# Control_Unit_and_Power.net
KiCad netlist of a schematic drawn in Altium Designer
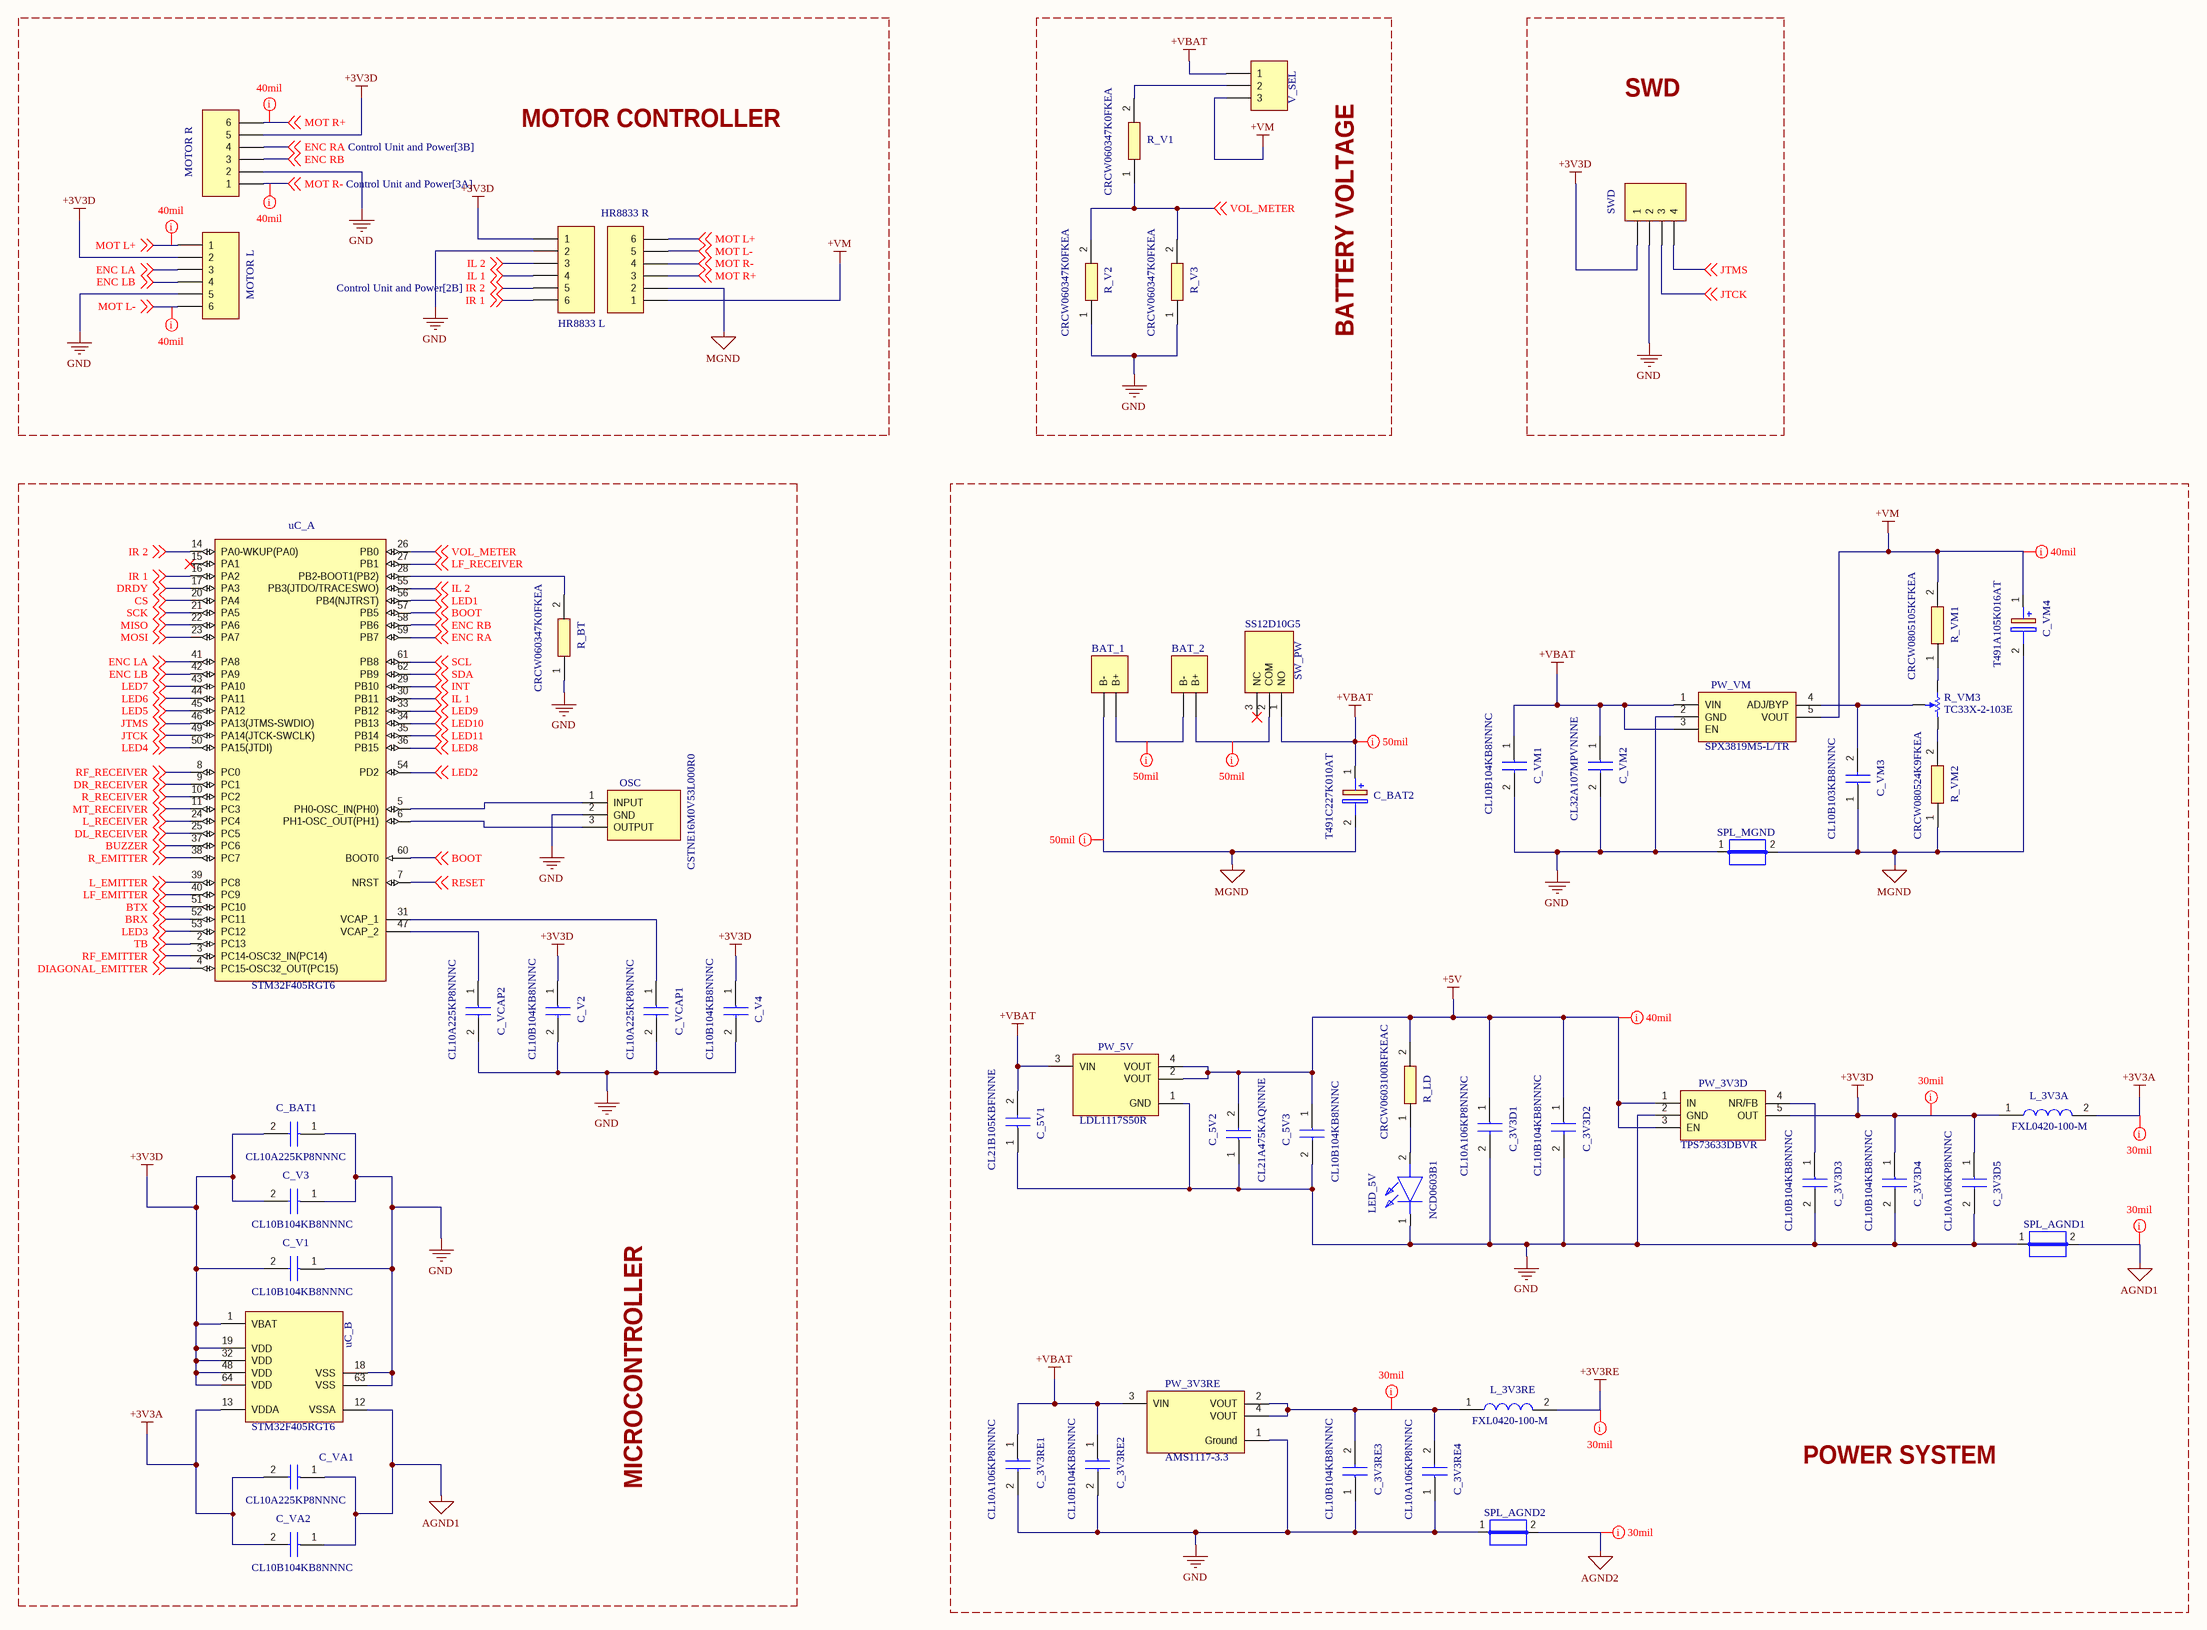
[diagram p0: Control Unit and Power.SchDoc]

(export (version "E")
  (design (tool "Eeschema 10.0.6"))
  (components
    (comp (ref "BAT_1")
      (value "Header 2")
      (footprint "MY_6410-02")
      (description "Header, 2-Pin")
      (fields (field (name "ASID PART NUMBER") "Header 2-AS"))
      (libsource (lib "Mylib+Rev+4") (part "Header 2"))
    )
    (comp (ref "BAT_2")
      (value "Header 2")
      (footprint "MY_6410-02")
      (description "Header, 2-Pin")
      (fields (field (name "ASID PART NUMBER") "Header 2-AS"))
      (libsource (lib "Mylib+Rev+4") (part "Header 2"))
    )
    (comp (ref "C_3V3D1")
      (value "CL10A106KP8NNNC")
      (footprint "SamacSys:CAPC1608X90N")
      (description "Capacitor")
      (fields (field (name "MOUSER PART NUMBER") "187-CL10A106KP8NNNC"))
      (libsource (lib "*") (part "CL10A106KP8NNNC"))
    )
    (comp (ref "C_3V3D2")
      (value "CL10B104KB8NNNC")
      (footprint "SamacSys:CAPC1608X90N")
      (description "Capacitor")
      (fields (field (name "MOUSER PART NUMBER") "187-CL10B104KB8NNNC"))
      (libsource (lib "*") (part "CL10B104KB8NNNC"))
    )
    (comp (ref "C_3V3D3")
      (value "CL10B104KB8NNNC")
      (footprint "SamacSys:CAPC1608X90N")
      (description "Capacitor")
      (fields (field (name "MOUSER PART NUMBER") "187-CL10B104KB8NNNC"))
      (libsource (lib "*") (part "CL10B104KB8NNNC"))
    )
    (comp (ref "C_3V3D4")
      (value "CL10B104KB8NNNC")
      (footprint "SamacSys:CAPC1608X90N")
      (description "Capacitor")
      (fields (field (name "MOUSER PART NUMBER") "187-CL10B104KB8NNNC"))
      (libsource (lib "*") (part "CL10B104KB8NNNC"))
    )
    (comp (ref "C_3V3D5")
      (value "CL10A106KP8NNNC")
      (footprint "SamacSys:CAPC1608X90N")
      (description "Capacitor")
      (fields (field (name "MOUSER PART NUMBER") "187-CL10A106KP8NNNC"))
      (libsource (lib "*") (part "CL10A106KP8NNNC"))
    )
    (comp (ref "C_3V3RE1")
      (value "CL10A106KP8NNNC")
      (footprint "SamacSys:CAPC1608X90N")
      (description "Capacitor")
      (fields (field (name "MOUSER PART NUMBER") "187-CL10A106KP8NNNC"))
      (libsource (lib "*") (part "CL10A106KP8NNNC"))
    )
    (comp (ref "C_3V3RE2")
      (value "CL10B104KB8NNNC")
      (footprint "SamacSys:CAPC1608X90N")
      (description "Capacitor")
      (fields (field (name "MOUSER PART NUMBER") "187-CL10B104KB8NNNC"))
      (libsource (lib "*") (part "CL10B104KB8NNNC"))
    )
    (comp (ref "C_3V3RE3")
      (value "CL10B104KB8NNNC")
      (footprint "SamacSys:CAPC1608X90N")
      (description "Capacitor")
      (fields (field (name "MOUSER PART NUMBER") "187-CL10B104KB8NNNC"))
      (libsource (lib "*") (part "CL10B104KB8NNNC"))
    )
    (comp (ref "C_3V3RE4")
      (value "CL10A106KP8NNNC")
      (footprint "SamacSys:CAPC1608X90N")
      (description "Capacitor")
      (fields (field (name "MOUSER PART NUMBER") "187-CL10A106KP8NNNC"))
      (libsource (lib "*") (part "CL10A106KP8NNNC"))
    )
    (comp (ref "C_5V1")
      (value "CL21B105KBFNNNE")
      (footprint "SamacSys:CAPC2012X135N")
      (description "Capacitor")
      (fields (field (name "MOUSER PART NUMBER") "187-CL21B105KBFNNNE"))
      (libsource (lib "*") (part "CL21B105KBFNNNE"))
    )
    (comp (ref "C_5V2")
      (value "CL21A475KAQNNNE")
      (footprint "SamacSys:CAPC2012X140N")
      (description "Capacitor")
      (fields (field (name "MOUSER PART NUMBER") "187-CL21A475KAQNNNE"))
      (libsource (lib "*") (part "CL21A475KAQNNNE"))
    )
    (comp (ref "C_5V3")
      (value "CL10B104KB8NNNC")
      (footprint "SamacSys:CAPC1608X90N")
      (description "Capacitor")
      (fields (field (name "MOUSER PART NUMBER") "187-CL10B104KB8NNNC"))
      (libsource (lib "*") (part "CL10B104KB8NNNC"))
    )
    (comp (ref "C_BAT1")
      (value "CL10A225KP8NNNC")
      (footprint "SamacSys:CAPC1608X90N")
      (description "Capacitor")
      (fields (field (name "MOUSER PART NUMBER") "187-CL10A225KP8NNNC"))
      (libsource (lib "*") (part "CL10A225KP8NNNC"))
    )
    (comp (ref "C_BAT2")
      (value "T491C227K010AT")
      (footprint "SamacSys:T491C")
      (description "Capacitor Polarised")
      (fields (field (name "MOUSER PART NUMBER") "80-T491C227K010AT"))
      (libsource (lib "*") (part "T491C227K010AT"))
    )
    (comp (ref "C_V1")
      (value "CL10B104KB8NNNC")
      (footprint "SamacSys:CAPC1608X90N")
      (description "Capacitor")
      (fields (field (name "MOUSER PART NUMBER") "187-CL10B104KB8NNNC"))
      (libsource (lib "*") (part "CL10B104KB8NNNC"))
    )
    (comp (ref "C_V2")
      (value "CL10B104KB8NNNC")
      (footprint "SamacSys:CAPC1608X90N")
      (description "Capacitor")
      (fields (field (name "MOUSER PART NUMBER") "187-CL10B104KB8NNNC"))
      (libsource (lib "*") (part "CL10B104KB8NNNC"))
    )
    (comp (ref "C_V3")
      (value "CL10B104KB8NNNC")
      (footprint "SamacSys:CAPC1608X90N")
      (description "Capacitor")
      (fields (field (name "MOUSER PART NUMBER") "187-CL10B104KB8NNNC"))
      (libsource (lib "*") (part "CL10B104KB8NNNC"))
    )
    (comp (ref "C_V4")
      (value "CL10B104KB8NNNC")
      (footprint "SamacSys:CAPC1608X90N")
      (description "Capacitor")
      (fields (field (name "MOUSER PART NUMBER") "187-CL10B104KB8NNNC"))
      (libsource (lib "*") (part "CL10B104KB8NNNC"))
    )
    (comp (ref "C_VA1")
      (value "CL10A225KP8NNNC")
      (footprint "SamacSys:CAPC1608X90N")
      (description "Capacitor")
      (fields (field (name "MOUSER PART NUMBER") "187-CL10A225KP8NNNC"))
      (libsource (lib "*") (part "CL10A225KP8NNNC"))
    )
    (comp (ref "C_VA2")
      (value "CL10B104KB8NNNC")
      (footprint "SamacSys:CAPC1608X90N")
      (description "Capacitor")
      (fields (field (name "MOUSER PART NUMBER") "187-CL10B104KB8NNNC"))
      (libsource (lib "*") (part "CL10B104KB8NNNC"))
    )
    (comp (ref "C_VCAP1")
      (value "CL10A225KP8NNNC")
      (footprint "SamacSys:CAPC1608X90N")
      (description "Capacitor")
      (fields (field (name "MOUSER PART NUMBER") "187-CL10A225KP8NNNC"))
      (libsource (lib "*") (part "CL10A225KP8NNNC"))
    )
    (comp (ref "C_VCAP2")
      (value "CL10A225KP8NNNC")
      (footprint "SamacSys:CAPC1608X90N")
      (description "Capacitor")
      (fields (field (name "MOUSER PART NUMBER") "187-CL10A225KP8NNNC"))
      (libsource (lib "*") (part "CL10A225KP8NNNC"))
    )
    (comp (ref "C_VM1")
      (value "CL10B104KB8NNNC")
      (footprint "SamacSys:CAPC1608X90N")
      (description "Capacitor")
      (fields (field (name "MOUSER PART NUMBER") "187-CL10B104KB8NNNC"))
      (libsource (lib "*") (part "CL10B104KB8NNNC"))
    )
    (comp (ref "C_VM2")
      (value "CL32A107MPVNNNE")
      (footprint "SamacSys:CAPC3225X280N")
      (description "Capacitor")
      (fields (field (name "MOUSER PART NUMBER") "187-CL32A107MPVNNNE"))
      (libsource (lib "*") (part "CL32A107MPVNNNE"))
    )
    (comp (ref "C_VM3")
      (value "CL10B103KB8NNNC")
      (footprint "SamacSys:CAPC1608X90N")
      (description "Capacitor")
      (fields (field (name "MOUSER PART NUMBER") "187-CL10B103KB8NNNC"))
      (libsource (lib "*") (part "CL10B103KB8NNNC"))
    )
    (comp (ref "C_VM4")
      (value "T491A105K016AT")
      (footprint "SamacSys:T491A")
      (description "Capacitor Polarised")
      (fields (field (name "MOUSER PART NUMBER") "80-T491A105K016"))
      (libsource (lib "*") (part "T491A105K016AT"))
    )
    (comp (ref "HR8833 L")
      (value "Header 6")
      (footprint "My_1X06")
      (description "Header, 6-Pin")
      (fields (field (name "ASID PART NUMBER") "Header 6-AS"))
      (libsource (lib "Mylib+Rev+4") (part "Header 6"))
    )
    (comp (ref "HR8833 R")
      (value "Header 6")
      (footprint "My_1X06")
      (description "Header, 6-Pin")
      (fields (field (name "ASID PART NUMBER") "Header 6-AS"))
      (libsource (lib "") (part "Header 6_1"))
    )
    (comp (ref "LED_5V")
      (value "NCD0603B1")
      (footprint "SamacSys:LEDC1608X40N")
      (fields
        (field (name "MANUFACTURER_PART_NUMBER") "LB Q39E-L2OO-35-1")
        (field (name "MOUSER PART NUMBER") "720-LBQ39EL2N2351")
      )
      (libsource (lib "*") (part "LB_Q39E-L2OO-35-1"))
    )
    (comp (ref "L_3V3A")
      (value "FXL0420-100-M")
      (footprint "SamacSys:INDPM4441X120N")
      (description "1.6A 10uH Integrated molded inductor ±20% 2.2A SMD,4.2x4.4mm Power Inductors ROHS")
      (fields
        (field (name "MANUFACTURER_PART_NUMBER") "PM4546.331NLT")
        (field (name "MOUSER PART NUMBER") "673-PM4546.331NLT")
      )
      (libsource (lib "*") (part "PM4546.331NLT"))
    )
    (comp (ref "L_3V3RE")
      (value "FXL0420-100-M")
      (footprint "SamacSys:INDPM4441X120N")
      (description "1.6A 10uH Integrated molded inductor ±20% 2.2A SMD,4.2x4.4mm Power Inductors ROHS")
      (fields
        (field (name "MANUFACTURER_PART_NUMBER") "PM4546.331NLT")
        (field (name "MOUSER PART NUMBER") "673-PM4546.331NLT")
      )
      (libsource (lib "*") (part "PM4546.331NLT"))
    )
    (comp (ref "MOTOR L")
      (value "Header 6")
      (footprint "MY_53253-0670")
      (description "Header, 6-Pin")
      (fields (field (name "ASID PART NUMBER") "Header 6-AS"))
      (libsource (lib "Mylib+Rev+4") (part "Header 6"))
    )
    (comp (ref "MOTOR R")
      (value "Header 6")
      (footprint "MY_53253-0670")
      (description "Header, 6-Pin")
      (fields (field (name "ASID PART NUMBER") "Header 6-AS"))
      (libsource (lib "") (part "Header 6_1"))
    )
    (comp (ref "OSC")
      (value "CSTNE16M0V53L000R0")
      (footprint "SamacSys:CSTNE16M0V53L000R0")
      (description "Crystal or Oscillator")
      (fields (field (name "MOUSER PART NUMBER") "81-CSTNE16M0V53L000R"))
      (libsource (lib "*") (part "CSTNE16M0V53L000R0"))
    )
    (comp (ref "PW_3V3D")
      (value "TPS73633DBVR")
      (footprint "SamacSys:SOT95P280X145-5N")
      (description "Integrated Circuit")
      (fields (field (name "MOUSER PART NUMBER") "595-TPS73633DBVR"))
      (libsource (lib "*") (part "TPS73633DBVR"))
    )
    (comp (ref "PW_3V3RE")
      (value "AMS1117-3.3")
      (footprint "FP-AMS1117-IPC_C")
      (description "LDO Voltage Regulators 1A, 3.3V")
      (fields
        (field (name "OCTOPART") "https://octopart.com/ams1117-3.3-advanced+monolithic+systems-25899300")
        (field (name "MANUFACTURER") "Advanced Monolithic Systems")
      )
      (libsource (lib "Altium Content Vault") (part "8bdbb5f8e77002000e30dd2845d0354"))
    )
    (comp (ref "PW_5V")
      (value "LDL1117S50R")
      (footprint "FP-SOT-223-0046067_14-MFG")
      (description "IC REG LINEAR 5V 1.2A SOT223")
      (fields
        (field (name "OCTOPART") "https://octopart.com/ldl1117s50r-stmicroelectronics-81876164")
        (field (name "MANUFACTURER") "STMicroelectronics")
      )
      (libsource (lib "Altium Content Vault") (part "a368f1d72361ca9956852d636243424"))
    )
    (comp (ref "PW_VM")
      (value "SPX3819M5-L/TR")
      (footprint "SamacSys:SOT95P280X145-5N")
      (description "Integrated Circuit")
      (fields (field (name "MOUSER PART NUMBER") "701-SPX3819M5-L/TR"))
      (libsource (lib "*") (part "SPX3819M5-L_TR"))
    )
    (comp (ref "R_BT")
      (value "CRCW060347K0FKEA")
      (footprint "SamacSys:RESC1608X50N")
      (description "Resistor")
      (fields (field (name "MOUSER PART NUMBER") "71-CRCW0603-47K-E3"))
      (libsource (lib "*") (part "CRCW060347K0FKEA"))
    )
    (comp (ref "R_LD")
      (value "CRCW0603100RFKEAC")
      (footprint "SamacSys:RESC1608X55N")
      (description "Resistor")
      (fields (field (name "MOUSER PART NUMBER") "71-CRCW0603100RFKEAC"))
      (libsource (lib "*") (part "CRCW0603100RFKEAC"))
    )
    (comp (ref "R_V1")
      (value "CRCW060347K0FKEA")
      (footprint "SamacSys:RESC1608X50N")
      (description "Resistor")
      (fields (field (name "MOUSER PART NUMBER") "71-CRCW0603-47K-E3"))
      (libsource (lib "*") (part "CRCW060347K0FKEA"))
    )
    (comp (ref "R_V2")
      (value "CRCW060347K0FKEA")
      (footprint "SamacSys:RESC1608X50N")
      (description "Resistor")
      (fields (field (name "MOUSER PART NUMBER") "71-CRCW0603-47K-E3"))
      (libsource (lib "*") (part "CRCW060347K0FKEA"))
    )
    (comp (ref "R_V3")
      (value "CRCW060347K0FKEA")
      (footprint "SamacSys:RESC1608X50N")
      (description "Resistor")
      (fields (field (name "MOUSER PART NUMBER") "71-CRCW0603-47K-E3"))
      (libsource (lib "*") (part "CRCW060347K0FKEA"))
    )
    (comp (ref "R_VM1")
      (value "CRCW0805105KFKEA")
      (footprint "SamacSys:RESC2012X50N")
      (description "Resistor")
      (fields (field (name "MOUSER PART NUMBER") "71-CRCW0805-105K-E3"))
      (libsource (lib "*") (part "CRCW0805105KFKEA"))
    )
    (comp (ref "R_VM2")
      (value "CRCW080524K9FKEA")
      (footprint "SamacSys:RESC2012X50N")
      (description "Resistor")
      (fields (field (name "MOUSER PART NUMBER") "71-CRCW0805-24.9K-E3"))
      (libsource (lib "*") (part "CRCW080524K9FKEA"))
    )
    (comp (ref "R_VM3")
      (value "TC33X-2-103E")
      (footprint "BOUR-TC33X-2_V")
      (description "Trimming Potentiometer, 10000 Ohm, -40 to 100 degC, 3-Pin SMD, RoHS, Tape and Reel")
      (fields (field (name "TOLERANCE") "25%") (field (name "MANUFACTURER") "Bourns"))
      (libsource (lib "Altium Content Vault") (part "RES-ADJ-3_A"))
    )
    (comp (ref "SPL_AGND1")
      (value "JUMPER")
      (footprint "JUMPER")
      (libsource (lib "University of Moratuwa") (part "JUMPER"))
    )
    (comp (ref "SPL_AGND2")
      (value "JUMPER")
      (footprint "JUMPER")
      (libsource (lib "University of Moratuwa") (part "JUMPER"))
    )
    (comp (ref "SPL_MGND")
      (value "JUMPER")
      (footprint "JUMPER")
      (libsource (lib "University of Moratuwa") (part "JUMPER"))
    )
    (comp (ref "SWD")
      (value "Header 4")
      (footprint "MY_FE04")
      (description "Header, 4-Pin")
      (fields (field (name "ASID PART NUMBER") "Header 4-AS"))
      (libsource (lib "Mylib+Rev+4") (part "Header 4"))
    )
    (comp (ref "SW_PW")
      (value "SS12D10G5")
      (footprint "SamacSys:GH36P010001")
      (description "Bend insert 2A Single Pole Double Throw (SPDT) 125V 3000 times Black Plugin Slide Switches ROHS")
      (fields
        (field (name "MANUFACTURER_PART_NUMBER") "GH36P010001")
        (field (name "MOUSER PART NUMBER") "642-GH36P010001")
      )
      (libsource (lib "*") (part "GH36P010001"))
    )
    (comp (ref "uC_")
      (value "STM32F405RGT6")
      (footprint "STM-LQFP64_V")
      (fields (field (name "MANUFACTURER") "STMicroelectronics"))
      (libsource (lib "Altium Content Vault") (part "MC-ARM-STM32F4X5-SQ64"))
    )
    (comp (ref "V_SEL")
      (value "Header 3")
      (footprint "My_1X03")
      (description "Header, 3-Pin")
      (fields (field (name "ASID PART NUMBER") "Header 3-AS"))
      (libsource (lib "Mylib+Rev+4") (part "Header 3"))
    )
  )
  (nets
    (net (code "1") (name "+3V3A") (class "Default")
      (node (ref "C_VA1") (pin "2") (pinfunction "2_2") (pintype "passive"))
      (node (ref "C_VA2") (pin "2") (pinfunction "2_2") (pintype "passive"))
      (node (ref "L_3V3A") (pin "2") (pinfunction "2_2") (pintype "passive"))
      (node (ref "uC_") (pin "13") (pinfunction "VDDA_13") (pintype "power_in"))
    )
    (net (code "2") (name "+3V3D") (class "Default")
      (node (ref "C_3V3D4") (pin "1") (pinfunction "1_1") (pintype "passive"))
      (node (ref "C_3V3D5") (pin "1") (pinfunction "1_1") (pintype "passive"))
      (node (ref "C_BAT1") (pin "2") (pinfunction "2_2") (pintype "passive"))
      (node (ref "C_V1") (pin "2") (pinfunction "2_2") (pintype "passive"))
      (node (ref "C_V2") (pin "1") (pinfunction "1_1") (pintype "passive"))
      (node (ref "C_V3") (pin "2") (pinfunction "2_2") (pintype "passive"))
      (node (ref "C_V4") (pin "1") (pinfunction "1_1") (pintype "passive"))
      (node (ref "HR8833 L") (pin "1") (pinfunction "1_1") (pintype "passive"))
      (node (ref "L_3V3A") (pin "1") (pinfunction "1_1") (pintype "passive"))
      (node (ref "MOTOR L") (pin "2") (pinfunction "2_2") (pintype "passive"))
      (node (ref "MOTOR R") (pin "5") (pinfunction "5_5") (pintype "passive"))
      (node (ref "PW_3V3D") (pin "5") (pinfunction "OUT_5") (pintype "passive"))
      (node (ref "SWD") (pin "1") (pinfunction "1_1") (pintype "passive"))
      (node (ref "uC_") (pin "1") (pinfunction "VBAT_1") (pintype "power_in"))
      (node (ref "uC_") (pin "19") (pinfunction "VDD_19") (pintype "power_in"))
      (node (ref "uC_") (pin "32") (pinfunction "VDD_32") (pintype "power_in"))
      (node (ref "uC_") (pin "48") (pinfunction "VDD_48") (pintype "power_in"))
      (node (ref "uC_") (pin "64") (pinfunction "VDD_64") (pintype "power_in"))
    )
    (net (code "3") (name "+3V3RE") (class "Default")
      (node (ref "L_3V3RE") (pin "2") (pinfunction "2_2") (pintype "passive"))
    )
    (net (code "4") (name "+5V") (class "Default")
      (node (ref "C_3V3D1") (pin "1") (pinfunction "1_1") (pintype "passive"))
      (node (ref "C_3V3D2") (pin "1") (pinfunction "1_1") (pintype "passive"))
      (node (ref "C_5V2") (pin "2") (pinfunction "2_2") (pintype "passive"))
      (node (ref "C_5V3") (pin "1") (pinfunction "1_1") (pintype "passive"))
      (node (ref "PW_3V3D") (pin "1") (pinfunction "IN_1") (pintype "passive"))
      (node (ref "PW_3V3D") (pin "3") (pinfunction "EN_3") (pintype "passive"))
      (node (ref "PW_5V") (pin "2") (pinfunction "VOUT_2") (pintype "power_in"))
      (node (ref "PW_5V") (pin "4") (pinfunction "VOUT_4") (pintype "power_in"))
      (node (ref "R_LD") (pin "2") (pinfunction "2_2") (pintype "passive"))
    )
    (net (code "5") (name "+VBAT") (class "Default")
      (node (ref "C_3V3RE1") (pin "1") (pinfunction "1_1") (pintype "passive"))
      (node (ref "C_3V3RE2") (pin "1") (pinfunction "1_1") (pintype "passive"))
      (node (ref "C_5V1") (pin "2") (pinfunction "2_2") (pintype "passive"))
      (node (ref "C_BAT2") (pin "1") (pinfunction "+_1") (pintype "passive"))
      (node (ref "C_VM1") (pin "1") (pinfunction "1_1") (pintype "passive"))
      (node (ref "C_VM2") (pin "1") (pinfunction "1_1") (pintype "passive"))
      (node (ref "PW_3V3RE") (pin "3") (pinfunction "VIN_3") (pintype "power_in"))
      (node (ref "PW_5V") (pin "3") (pinfunction "VIN_3") (pintype "power_in"))
      (node (ref "PW_VM") (pin "1") (pinfunction "VIN_1") (pintype "passive"))
      (node (ref "PW_VM") (pin "3") (pinfunction "EN_3") (pintype "passive"))
      (node (ref "SW_PW") (pin "1") (pinfunction "NO_1") (pintype "passive"))
      (node (ref "V_SEL") (pin "1") (pinfunction "1_1") (pintype "passive"))
    )
    (net (code "6") (name "+VM") (class "Default")
      (node (ref "C_VM4") (pin "1") (pinfunction "+_1") (pintype "passive"))
      (node (ref "HR8833 R") (pin "1") (pinfunction "1_1") (pintype "passive"))
      (node (ref "PW_VM") (pin "5") (pinfunction "VOUT_5") (pintype "passive"))
      (node (ref "R_VM1") (pin "2") (pinfunction "2_2") (pintype "passive"))
      (node (ref "V_SEL") (pin "3") (pinfunction "3_3") (pintype "passive"))
    )
    (net (code "7") (name "AGND1") (class "Default")
      (node (ref "C_VA1") (pin "1") (pinfunction "1_1") (pintype "passive"))
      (node (ref "C_VA2") (pin "1") (pinfunction "1_1") (pintype "passive"))
      (node (ref "SPL_AGND1") (pin "2") (pinfunction "2_2") (pintype "passive"))
      (node (ref "uC_") (pin "12") (pinfunction "VSSA_12") (pintype "power_in"))
    )
    (net (code "8") (name "AGND2") (class "Default")
      (node (ref "SPL_AGND2") (pin "2") (pinfunction "2_2") (pintype "passive"))
    )
    (net (code "9") (name "BOOT") (class "Default")
      (node (ref "uC_") (pin "57") (pinfunction "PB5_57") (pintype "bidirectional"))
      (node (ref "uC_") (pin "60") (pinfunction "BOOT0_60") (pintype "input"))
    )
    (net (code "10") (name "BRX") (class "Default")
      (node (ref "uC_") (pin "52") (pinfunction "PC11_52") (pintype "bidirectional"))
    )
    (net (code "11") (name "BTX") (class "Default")
      (node (ref "uC_") (pin "51") (pinfunction "PC10_51") (pintype "bidirectional"))
    )
    (net (code "12") (name "BUZZER") (class "Default")
      (node (ref "uC_") (pin "37") (pinfunction "PC6_37") (pintype "bidirectional"))
    )
    (net (code "13") (name "CS") (class "Default")
      (node (ref "uC_") (pin "20") (pinfunction "PA4_20") (pintype "bidirectional"))
    )
    (net (code "14") (name "DIAGONAL_EMITTER") (class "Default")
      (node (ref "uC_") (pin "4") (pinfunction "PC15-OSC32_OUT(PC15)_4") (pintype "bidirectional"))
    )
    (net (code "15") (name "DL_RECEIVER") (class "Default")
      (node (ref "uC_") (pin "25") (pinfunction "PC5_25") (pintype "bidirectional"))
    )
    (net (code "16") (name "DRDY") (class "Default")
      (node (ref "uC_") (pin "17") (pinfunction "PA3_17") (pintype "bidirectional"))
    )
    (net (code "17") (name "DR_RECEIVER") (class "Default")
      (node (ref "uC_") (pin "9") (pinfunction "PC1_9") (pintype "bidirectional"))
    )
    (net (code "18") (name "ENC LA") (class "Default")
      (node (ref "MOTOR L") (pin "3") (pinfunction "3_3") (pintype "passive"))
      (node (ref "uC_") (pin "41") (pinfunction "PA8_41") (pintype "bidirectional"))
    )
    (net (code "19") (name "ENC LB") (class "Default")
      (node (ref "MOTOR L") (pin "4") (pinfunction "4_4") (pintype "passive"))
      (node (ref "uC_") (pin "42") (pinfunction "PA9_42") (pintype "bidirectional"))
    )
    (net (code "20") (name "ENC RA") (class "Default")
      (node (ref "MOTOR R") (pin "4") (pinfunction "4_4") (pintype "passive"))
      (node (ref "uC_") (pin "59") (pinfunction "PB7_59") (pintype "bidirectional"))
    )
    (net (code "21") (name "ENC RB") (class "Default")
      (node (ref "MOTOR R") (pin "3") (pinfunction "3_3") (pintype "passive"))
      (node (ref "uC_") (pin "58") (pinfunction "PB6_58") (pintype "bidirectional"))
    )
    (net (code "22") (name "GND") (class "Default")
      (node (ref "C_3V3D1") (pin "2") (pinfunction "2_2") (pintype "passive"))
      (node (ref "C_3V3D2") (pin "2") (pinfunction "2_2") (pintype "passive"))
      (node (ref "C_3V3D3") (pin "2") (pinfunction "2_2") (pintype "passive"))
      (node (ref "C_3V3D4") (pin "2") (pinfunction "2_2") (pintype "passive"))
      (node (ref "C_3V3D5") (pin "2") (pinfunction "2_2") (pintype "passive"))
      (node (ref "C_3V3RE1") (pin "2") (pinfunction "2_2") (pintype "passive"))
      (node (ref "C_3V3RE2") (pin "2") (pinfunction "2_2") (pintype "passive"))
      (node (ref "C_3V3RE3") (pin "1") (pinfunction "1_1") (pintype "passive"))
      (node (ref "C_3V3RE4") (pin "1") (pinfunction "1_1") (pintype "passive"))
      (node (ref "C_5V1") (pin "1") (pinfunction "1_1") (pintype "passive"))
      (node (ref "C_5V2") (pin "1") (pinfunction "1_1") (pintype "passive"))
      (node (ref "C_5V3") (pin "2") (pinfunction "2_2") (pintype "passive"))
      (node (ref "C_BAT1") (pin "1") (pinfunction "1_1") (pintype "passive"))
      (node (ref "C_V1") (pin "1") (pinfunction "1_1") (pintype "passive"))
      (node (ref "C_V2") (pin "2") (pinfunction "2_2") (pintype "passive"))
      (node (ref "C_V3") (pin "1") (pinfunction "1_1") (pintype "passive"))
      (node (ref "C_V4") (pin "2") (pinfunction "2_2") (pintype "passive"))
      (node (ref "C_VCAP1") (pin "2") (pinfunction "2_2") (pintype "passive"))
      (node (ref "C_VCAP2") (pin "2") (pinfunction "2_2") (pintype "passive"))
      (node (ref "C_VM1") (pin "2") (pinfunction "2_2") (pintype "passive"))
      (node (ref "C_VM2") (pin "2") (pinfunction "2_2") (pintype "passive"))
      (node (ref "HR8833 L") (pin "2") (pinfunction "2_2") (pintype "passive"))
      (node (ref "LED_5V") (pin "1") (pinfunction "K_1") (pintype "passive"))
      (node (ref "MOTOR L") (pin "5") (pinfunction "5_5") (pintype "passive"))
      (node (ref "MOTOR R") (pin "2") (pinfunction "2_2") (pintype "passive"))
      (node (ref "OSC") (pin "2") (pinfunction "GND_2") (pintype "passive"))
      (node (ref "PW_3V3D") (pin "2") (pinfunction "GND_2") (pintype "passive"))
      (node (ref "PW_3V3RE") (pin "1") (pinfunction "Ground_1") (pintype "power_in"))
      (node (ref "PW_5V") (pin "1") (pinfunction "GND_1") (pintype "power_in"))
      (node (ref "PW_VM") (pin "2") (pinfunction "GND_2") (pintype "passive"))
      (node (ref "R_BT") (pin "1") (pinfunction "1_1") (pintype "passive"))
      (node (ref "R_V2") (pin "1") (pinfunction "1_1") (pintype "passive"))
      (node (ref "R_V3") (pin "1") (pinfunction "1_1") (pintype "passive"))
      (node (ref "SPL_AGND1") (pin "1") (pinfunction "1_1") (pintype "passive"))
      (node (ref "SPL_AGND2") (pin "1") (pinfunction "1_1") (pintype "passive"))
      (node (ref "SPL_MGND") (pin "1") (pinfunction "1_1") (pintype "passive"))
      (node (ref "SWD") (pin "2") (pinfunction "2_2") (pintype "passive"))
      (node (ref "uC_") (pin "18") (pinfunction "VSS_18") (pintype "power_in"))
      (node (ref "uC_") (pin "63") (pinfunction "VSS_63") (pintype "power_in"))
    )
    (net (code "23") (name "IL 1") (class "Default")
      (node (ref "HR8833 L") (pin "4") (pinfunction "4_4") (pintype "passive"))
      (node (ref "uC_") (pin "30") (pinfunction "PB11_30") (pintype "bidirectional"))
    )
    (net (code "24") (name "IL 2") (class "Default")
      (node (ref "HR8833 L") (pin "3") (pinfunction "3_3") (pintype "passive"))
      (node (ref "uC_") (pin "55") (pinfunction "PB3(JTDO/TRACESWO)_55") (pintype "bidirectional"))
    )
    (net (code "25") (name "INT") (class "Default")
      (node (ref "uC_") (pin "29") (pinfunction "PB10_29") (pintype "bidirectional"))
    )
    (net (code "26") (name "IR 1") (class "Default")
      (node (ref "HR8833 L") (pin "6") (pinfunction "6_6") (pintype "passive"))
      (node (ref "uC_") (pin "16") (pinfunction "PA2_16") (pintype "bidirectional"))
    )
    (net (code "27") (name "IR 2") (class "Default")
      (node (ref "HR8833 L") (pin "5") (pinfunction "5_5") (pintype "passive"))
      (node (ref "uC_") (pin "14") (pinfunction "PA0-WKUP(PA0)_14") (pintype "bidirectional"))
    )
    (net (code "28") (name "JTCK") (class "Default")
      (node (ref "SWD") (pin "3") (pinfunction "3_3") (pintype "passive"))
      (node (ref "uC_") (pin "49") (pinfunction "PA14(JTCK-SWCLK)_49") (pintype "bidirectional"))
    )
    (net (code "29") (name "JTMS") (class "Default")
      (node (ref "SWD") (pin "4") (pinfunction "4_4") (pintype "passive"))
      (node (ref "uC_") (pin "46") (pinfunction "PA13(JTMS-SWDIO)_46") (pintype "bidirectional"))
    )
    (net (code "30") (name "LED1") (class "Default")
      (node (ref "uC_") (pin "56") (pinfunction "PB4(NJTRST)_56") (pintype "bidirectional"))
    )
    (net (code "31") (name "LED2") (class "Default")
      (node (ref "uC_") (pin "54") (pinfunction "PD2_54") (pintype "bidirectional"))
    )
    (net (code "32") (name "LED3") (class "Default")
      (node (ref "uC_") (pin "53") (pinfunction "PC12_53") (pintype "bidirectional"))
    )
    (net (code "33") (name "LED4") (class "Default")
      (node (ref "uC_") (pin "50") (pinfunction "PA15(JTDI)_50") (pintype "bidirectional"))
    )
    (net (code "34") (name "LED5") (class "Default")
      (node (ref "uC_") (pin "45") (pinfunction "PA12_45") (pintype "bidirectional"))
    )
    (net (code "35") (name "LED6") (class "Default")
      (node (ref "uC_") (pin "44") (pinfunction "PA11_44") (pintype "bidirectional"))
    )
    (net (code "36") (name "LED7") (class "Default")
      (node (ref "uC_") (pin "43") (pinfunction "PA10_43") (pintype "bidirectional"))
    )
    (net (code "37") (name "LED8") (class "Default")
      (node (ref "uC_") (pin "36") (pinfunction "PB15_36") (pintype "bidirectional"))
    )
    (net (code "38") (name "LED9") (class "Default")
      (node (ref "uC_") (pin "33") (pinfunction "PB12_33") (pintype "bidirectional"))
    )
    (net (code "39") (name "LED10") (class "Default")
      (node (ref "uC_") (pin "34") (pinfunction "PB13_34") (pintype "bidirectional"))
    )
    (net (code "40") (name "LED11") (class "Default")
      (node (ref "uC_") (pin "35") (pinfunction "PB14_35") (pintype "bidirectional"))
    )
    (net (code "41") (name "LF_EMITTER") (class "Default")
      (node (ref "uC_") (pin "40") (pinfunction "PC9_40") (pintype "bidirectional"))
    )
    (net (code "42") (name "LF_RECEIVER") (class "Default")
      (node (ref "uC_") (pin "27") (pinfunction "PB1_27") (pintype "bidirectional"))
    )
    (net (code "43") (name "L_EMITTER") (class "Default")
      (node (ref "uC_") (pin "39") (pinfunction "PC8_39") (pintype "bidirectional"))
    )
    (net (code "44") (name "L_RECEIVER") (class "Default")
      (node (ref "uC_") (pin "24") (pinfunction "PC4_24") (pintype "bidirectional"))
    )
    (net (code "45") (name "MGND") (class "Default")
      (node (ref "BAT_1") (pin "2") (pinfunction "B-_2") (pintype "passive"))
      (node (ref "C_BAT2") (pin "2") (pinfunction "-_2") (pintype "passive"))
      (node (ref "C_VM3") (pin "1") (pinfunction "1_1") (pintype "passive"))
      (node (ref "C_VM4") (pin "2") (pinfunction "-_2") (pintype "passive"))
      (node (ref "HR8833 R") (pin "2") (pinfunction "2_2") (pintype "passive"))
      (node (ref "R_VM2") (pin "1") (pinfunction "1_1") (pintype "passive"))
      (node (ref "SPL_MGND") (pin "2") (pinfunction "2_2") (pintype "passive"))
    )
    (net (code "46") (name "MISO") (class "Default")
      (node (ref "uC_") (pin "22") (pinfunction "PA6_22") (pintype "bidirectional"))
    )
    (net (code "47") (name "MOSI") (class "Default")
      (node (ref "uC_") (pin "23") (pinfunction "PA7_23") (pintype "bidirectional"))
    )
    (net (code "48") (name "MOT L+") (class "Default")
      (node (ref "HR8833 R") (pin "6") (pinfunction "6_6") (pintype "passive"))
      (node (ref "MOTOR L") (pin "1") (pinfunction "1_1") (pintype "passive"))
    )
    (net (code "49") (name "MOT L-") (class "Default")
      (node (ref "HR8833 R") (pin "5") (pinfunction "5_5") (pintype "passive"))
      (node (ref "MOTOR L") (pin "6") (pinfunction "6_6") (pintype "passive"))
    )
    (net (code "50") (name "MOT R+") (class "Default")
      (node (ref "HR8833 R") (pin "3") (pinfunction "3_3") (pintype "passive"))
      (node (ref "MOTOR R") (pin "6") (pinfunction "6_6") (pintype "passive"))
    )
    (net (code "51") (name "MOT R-") (class "Default")
      (node (ref "HR8833 R") (pin "4") (pinfunction "4_4") (pintype "passive"))
      (node (ref "MOTOR R") (pin "1") (pinfunction "1_1") (pintype "passive"))
    )
    (net (code "52") (name "MT_RECEIVER") (class "Default")
      (node (ref "uC_") (pin "11") (pinfunction "PC3_11") (pintype "bidirectional"))
    )
    (net (code "53") (name "Net-(BAT_1-B+)") (class "Default")
      (node (ref "BAT_1") (pin "1") (pinfunction "B+_1") (pintype "passive"))
      (node (ref "BAT_2") (pin "2") (pinfunction "B-_2") (pintype "passive"))
    )
    (net (code "54") (name "Net-(BAT_2-B+)") (class "Default")
      (node (ref "BAT_2") (pin "1") (pinfunction "B+_1") (pintype "passive"))
      (node (ref "SW_PW") (pin "2") (pinfunction "COM_2") (pintype "passive"))
    )
    (net (code "55") (name "Net-(C_3V3RE3-Pad2)") (class "Default")
      (node (ref "C_3V3RE3") (pin "2") (pinfunction "2_2") (pintype "passive"))
      (node (ref "C_3V3RE4") (pin "2") (pinfunction "2_2") (pintype "passive"))
      (node (ref "L_3V3RE") (pin "1") (pinfunction "1_1") (pintype "passive"))
      (node (ref "PW_3V3RE") (pin "2") (pinfunction "VOUT_2") (pintype "passive"))
      (node (ref "PW_3V3RE") (pin "4") (pinfunction "VOUT_4") (pintype "passive"))
    )
    (net (code "56") (name "Net-(LED_5V-A)") (class "Default")
      (node (ref "LED_5V") (pin "2") (pinfunction "A_2") (pintype "passive"))
      (node (ref "R_LD") (pin "1") (pinfunction "1_1") (pintype "passive"))
    )
    (net (code "57") (name "Net-(OSC-INPUT)") (class "Default")
      (node (ref "OSC") (pin "1") (pinfunction "INPUT_1") (pintype "passive"))
      (node (ref "uC_") (pin "5") (pinfunction "PH0-OSC_IN(PH0)_5") (pintype "bidirectional"))
    )
    (net (code "58") (name "Net-(OSC-OUTPUT)") (class "Default")
      (node (ref "OSC") (pin "3") (pinfunction "OUTPUT_3") (pintype "passive"))
      (node (ref "uC_") (pin "6") (pinfunction "PH1-OSC_OUT(PH1)_6") (pintype "bidirectional"))
    )
    (net (code "59") (name "Net-(PW_3V3D-NR{slash}FB)") (class "Default")
      (node (ref "C_3V3D3") (pin "1") (pinfunction "1_1") (pintype "passive"))
      (node (ref "PW_3V3D") (pin "4") (pinfunction "NR/FB_4") (pintype "passive"))
    )
    (net (code "60") (name "Net-(PW_VM-ADJ{slash}BYP)") (class "Default")
      (node (ref "C_VM3") (pin "2") (pinfunction "2_2") (pintype "passive"))
      (node (ref "PW_VM") (pin "4") (pinfunction "ADJ/BYP_4") (pintype "passive"))
      (node (ref "R_VM3") (pin "2") (pinfunction "2_2") (pintype "passive"))
    )
    (net (code "61") (name "Net-(R_V1-Pad2)") (class "Default")
      (node (ref "R_V1") (pin "2") (pinfunction "2_2") (pintype "passive"))
      (node (ref "V_SEL") (pin "2") (pinfunction "2_2") (pintype "passive"))
    )
    (net (code "62") (name "Net-(R_VM1-Pad1)") (class "Default")
      (node (ref "R_VM1") (pin "1") (pinfunction "1_1") (pintype "passive"))
      (node (ref "R_VM3") (pin "1") (pinfunction "1_1") (pintype "passive"))
    )
    (net (code "63") (name "Net-(R_VM2-Pad2)") (class "Default")
      (node (ref "R_VM2") (pin "2") (pinfunction "2_2") (pintype "passive"))
      (node (ref "R_VM3") (pin "3") (pinfunction "3_3") (pintype "passive"))
    )
    (net (code "64") (name "Net-(uC_A-PB2-BOOT1(PB2))") (class "Default")
      (node (ref "R_BT") (pin "2") (pinfunction "2_2") (pintype "passive"))
      (node (ref "uC_") (pin "28") (pinfunction "PB2-BOOT1(PB2)_28") (pintype "bidirectional"))
    )
    (net (code "65") (name "Net-(uC_A-VCAP_1)") (class "Default")
      (node (ref "C_VCAP1") (pin "1") (pinfunction "1_1") (pintype "passive"))
      (node (ref "uC_") (pin "31") (pinfunction "VCAP_1_31") (pintype "power_in"))
    )
    (net (code "66") (name "Net-(uC_A-VCAP_2)") (class "Default")
      (node (ref "C_VCAP2") (pin "1") (pinfunction "1_1") (pintype "passive"))
      (node (ref "uC_") (pin "47") (pinfunction "VCAP_2_47") (pintype "power_in"))
    )
    (net (code "67") (name "RESET") (class "Default")
      (node (ref "uC_") (pin "7") (pinfunction "NRST_7") (pintype "bidirectional"))
    )
    (net (code "68") (name "RF_EMITTER") (class "Default")
      (node (ref "uC_") (pin "3") (pinfunction "PC14-OSC32_IN(PC14)_3") (pintype "bidirectional"))
    )
    (net (code "69") (name "RF_RECEIVER") (class "Default")
      (node (ref "uC_") (pin "8") (pinfunction "PC0_8") (pintype "bidirectional"))
    )
    (net (code "70") (name "R_EMITTER") (class "Default")
      (node (ref "uC_") (pin "38") (pinfunction "PC7_38") (pintype "bidirectional"))
    )
    (net (code "71") (name "R_RECEIVER") (class "Default")
      (node (ref "uC_") (pin "10") (pinfunction "PC2_10") (pintype "bidirectional"))
    )
    (net (code "72") (name "SCK") (class "Default")
      (node (ref "uC_") (pin "21") (pinfunction "PA5_21") (pintype "bidirectional"))
    )
    (net (code "73") (name "SCL") (class "Default")
      (node (ref "uC_") (pin "61") (pinfunction "PB8_61") (pintype "bidirectional"))
    )
    (net (code "74") (name "SDA") (class "Default")
      (node (ref "uC_") (pin "62") (pinfunction "PB9_62") (pintype "bidirectional"))
    )
    (net (code "75") (name "TB") (class "Default")
      (node (ref "uC_") (pin "2") (pinfunction "PC13_2") (pintype "bidirectional"))
    )
    (net (code "76") (name "VOL_METER") (class "Default")
      (node (ref "R_V1") (pin "1") (pinfunction "1_1") (pintype "passive"))
      (node (ref "R_V2") (pin "2") (pinfunction "2_2") (pintype "passive"))
      (node (ref "R_V3") (pin "2") (pinfunction "2_2") (pintype "passive"))
      (node (ref "uC_") (pin "26") (pinfunction "PB0_26") (pintype "bidirectional"))
    )
    (net (code "77") (name "unconnected-(SW_PW-NC-Pad3)") (class "Default")
      (node (ref "SW_PW") (pin "3") (pinfunction "NC_3") (pintype "passive+no_connect"))
    )
    (net (code "78") (name "unconnected-(uC_A-PA1-Pad15)") (class "Default")
      (node (ref "uC_") (pin "15") (pinfunction "PA1_15") (pintype "bidirectional+no_connect"))
    )
  )
)
